# Business_card_rev6.net
KiCad netlist of a schematic drawn in EAGLE
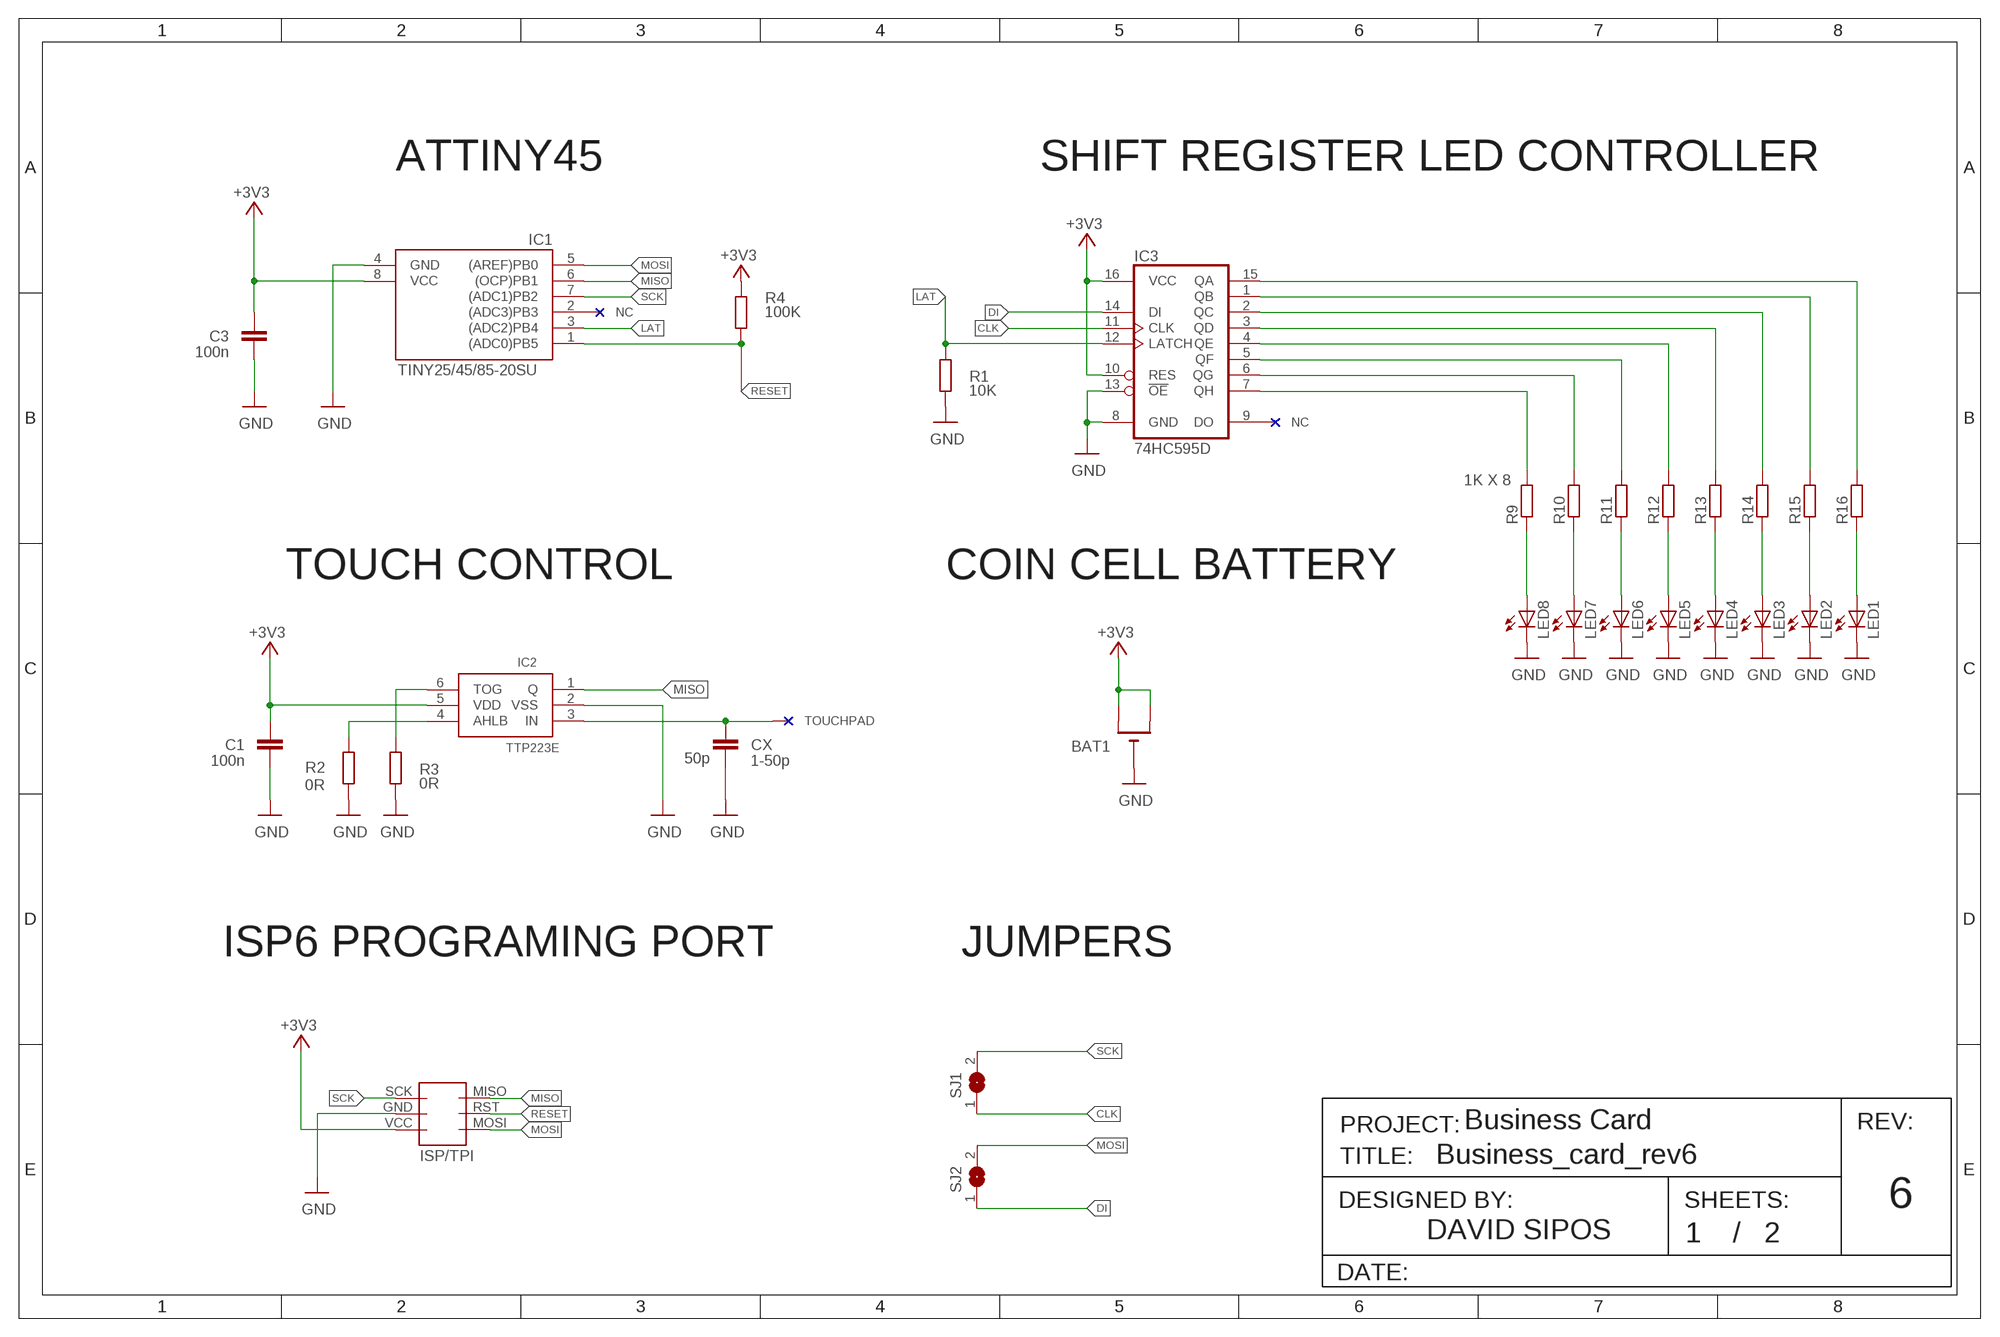
[diagram p0: schematic, sheet 1]
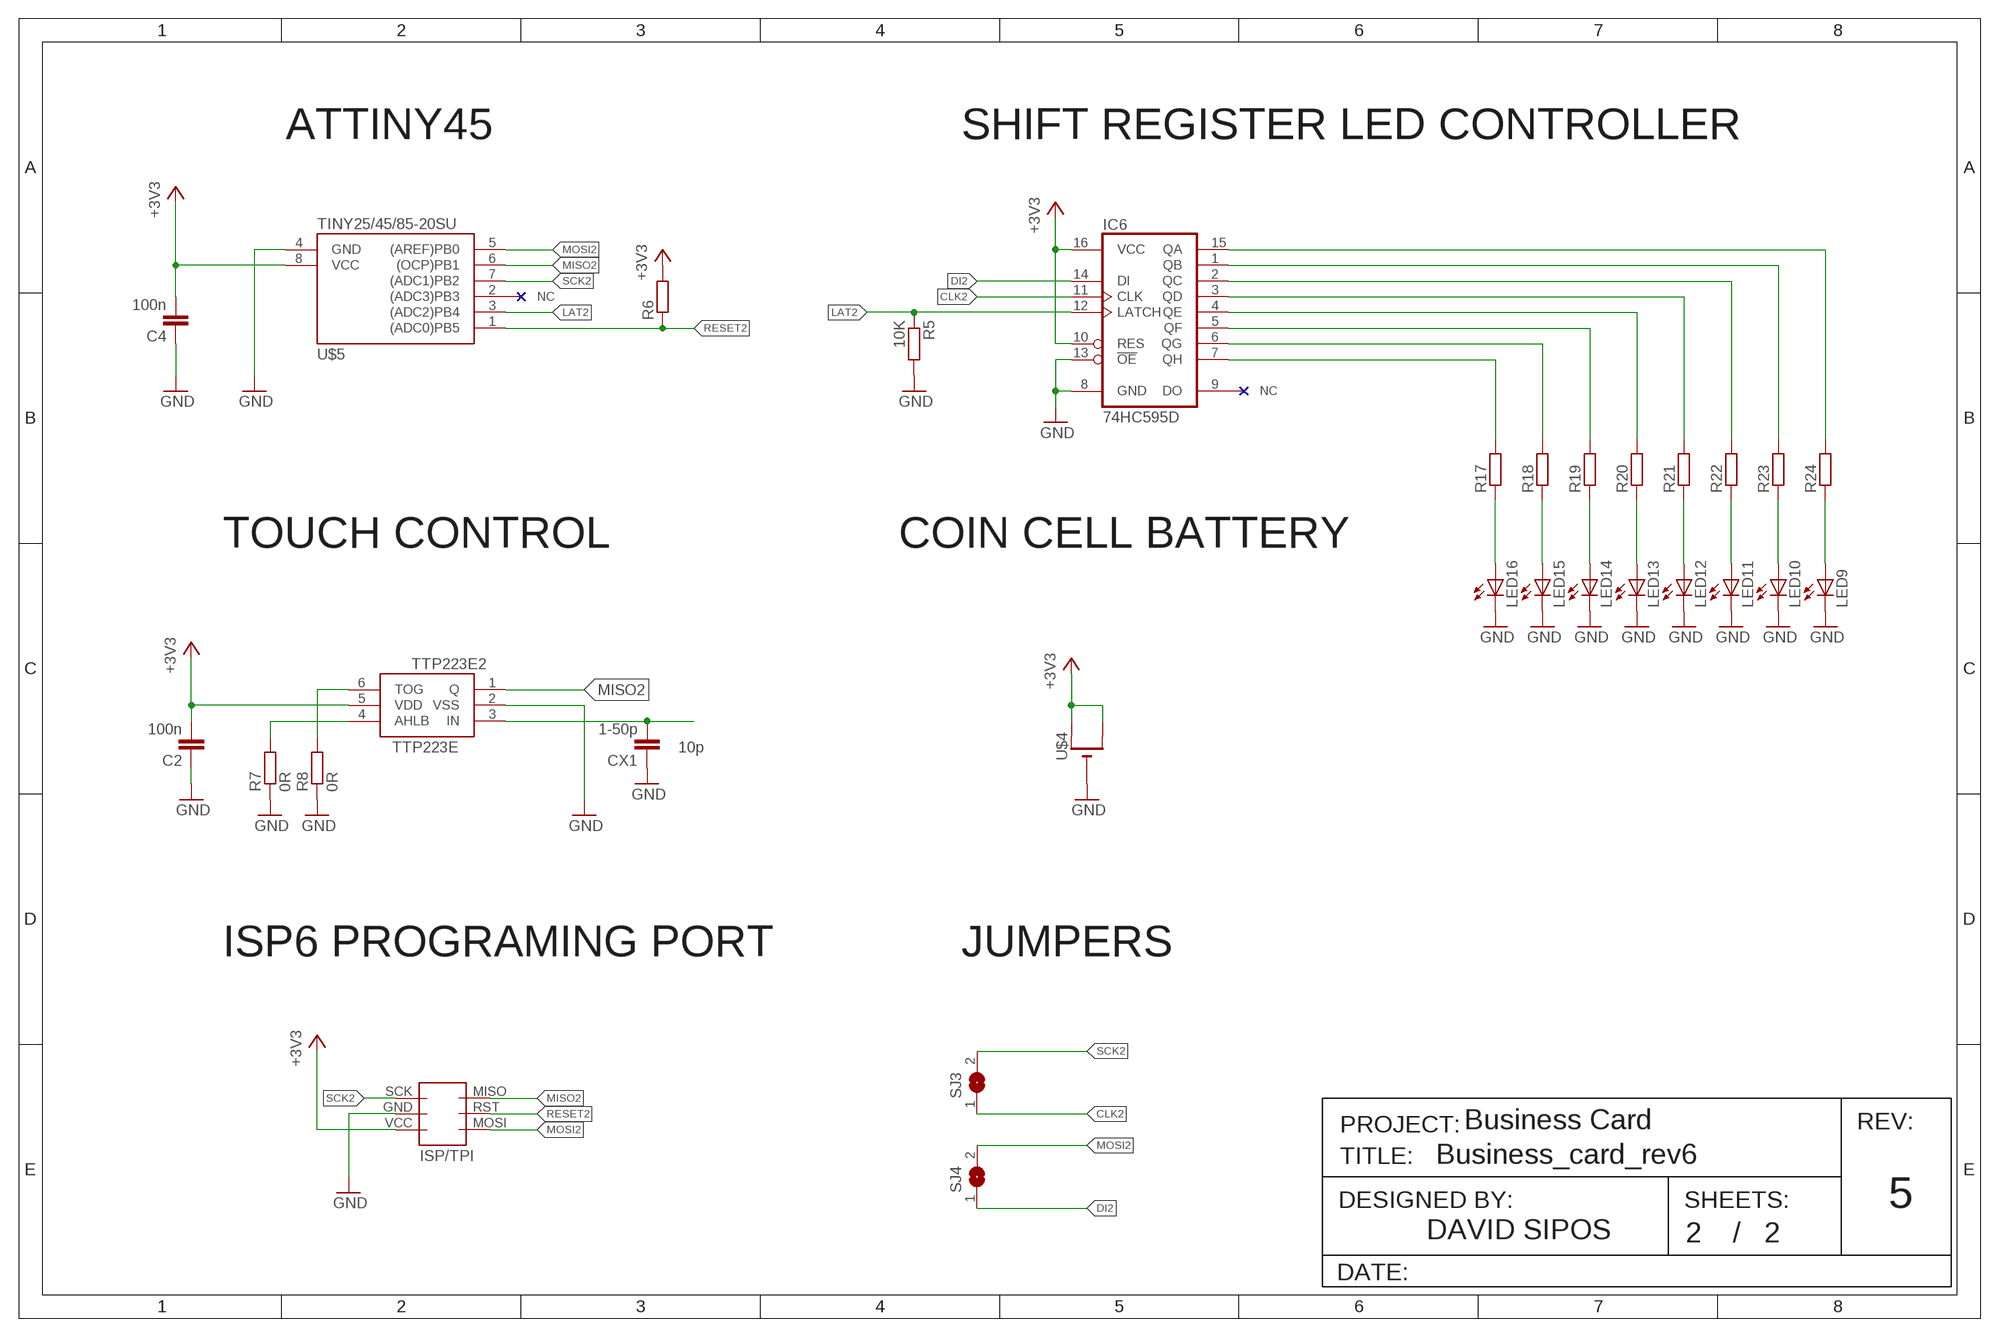
[diagram p1: schematic, sheet 2]

(export (version "E")
  (design (tool "Eeschema 10.0.6"))
  (components
    (comp (ref "BAT1")
      (value "CR2032SMT")
      (footprint "eagle-import:CR2032-SMD")
      (libsource (lib "eagle-import") (part "CR2032SMT"))
    )
    (comp (ref "C1")
      (value "100n")
      (footprint "eagle-import:C1206K")
      (libsource (lib "eagle-import") (part "C-EUC1206K"))
    )
    (comp (ref "C3")
      (value "100n")
      (footprint "eagle-import:C1206K")
      (libsource (lib "eagle-import") (part "C-EUC1206K"))
    )
    (comp (ref "CX")
      (value "1-50p")
      (footprint "eagle-import:C1206K")
      (libsource (lib "eagle-import") (part "C-EUC1206K"))
    )
    (comp (ref "IC1")
      (value "TINY25/45/85-20SU")
      (footprint "eagle-import:SOIC8")
      (libsource (lib "eagle-import") (part "TINY25/45/85-20SU"))
    )
    (comp (ref "IC2")
      (value "TTP223E")
      (footprint "eagle-import:SOT23-6")
      (libsource (lib "eagle-import") (part "TTP223E"))
    )
    (comp (ref "IC3")
      (value "74HC595D")
      (footprint "eagle-import:SO16")
      (libsource (lib "eagle-import") (part "74595DHC"))
    )
    (comp (ref "LED1")
      (value "LEDCHIPLED_0805")
      (footprint "eagle-import:CHIPLED_0805")
      (libsource (lib "eagle-import") (part "LEDCHIPLED_0805"))
    )
    (comp (ref "LED2")
      (value "LEDCHIPLED_0805")
      (footprint "eagle-import:CHIPLED_0805")
      (libsource (lib "eagle-import") (part "LEDCHIPLED_0805"))
    )
    (comp (ref "LED3")
      (value "LEDCHIPLED_0805")
      (footprint "eagle-import:CHIPLED_0805")
      (libsource (lib "eagle-import") (part "LEDCHIPLED_0805"))
    )
    (comp (ref "LED4")
      (value "LEDCHIPLED_0805")
      (footprint "eagle-import:CHIPLED_0805")
      (libsource (lib "eagle-import") (part "LEDCHIPLED_0805"))
    )
    (comp (ref "LED5")
      (value "LEDCHIPLED_0805")
      (footprint "eagle-import:CHIPLED_0805")
      (libsource (lib "eagle-import") (part "LEDCHIPLED_0805"))
    )
    (comp (ref "LED6")
      (value "LEDCHIPLED_0805")
      (footprint "eagle-import:CHIPLED_0805")
      (libsource (lib "eagle-import") (part "LEDCHIPLED_0805"))
    )
    (comp (ref "LED7")
      (value "LEDCHIPLED_0805")
      (footprint "eagle-import:CHIPLED_0805")
      (libsource (lib "eagle-import") (part "LEDCHIPLED_0805"))
    )
    (comp (ref "LED8")
      (value "LEDCHIPLED_0805")
      (footprint "eagle-import:CHIPLED_0805")
      (libsource (lib "eagle-import") (part "LEDCHIPLED_0805"))
    )
    (comp (ref "R1")
      (value "10K")
      (footprint "eagle-import:M0805")
      (libsource (lib "eagle-import") (part "R-EU_M0805"))
    )
    (comp (ref "R2")
      (value "0R")
      (footprint "eagle-import:M0805")
      (libsource (lib "eagle-import") (part "R-EU_M0805"))
    )
    (comp (ref "R3")
      (value "0R")
      (footprint "eagle-import:M0805")
      (libsource (lib "eagle-import") (part "R-EU_M0805"))
    )
    (comp (ref "R4")
      (value "100K")
      (footprint "eagle-import:M0805")
      (libsource (lib "eagle-import") (part "R-EU_M0805"))
    )
    (comp (ref "R9")
      (value "R-EU_M0805")
      (footprint "eagle-import:M0805")
      (libsource (lib "eagle-import") (part "R-EU_M0805"))
    )
    (comp (ref "R10")
      (value "R-EU_M0805")
      (footprint "eagle-import:M0805")
      (libsource (lib "eagle-import") (part "R-EU_M0805"))
    )
    (comp (ref "R11")
      (value "R-EU_M0805")
      (footprint "eagle-import:M0805")
      (libsource (lib "eagle-import") (part "R-EU_M0805"))
    )
    (comp (ref "R12")
      (value "R-EU_M0805")
      (footprint "eagle-import:M0805")
      (libsource (lib "eagle-import") (part "R-EU_M0805"))
    )
    (comp (ref "R13")
      (value "R-EU_M0805")
      (footprint "eagle-import:M0805")
      (libsource (lib "eagle-import") (part "R-EU_M0805"))
    )
    (comp (ref "R14")
      (value "R-EU_M0805")
      (footprint "eagle-import:M0805")
      (libsource (lib "eagle-import") (part "R-EU_M0805"))
    )
    (comp (ref "R15")
      (value "R-EU_M0805")
      (footprint "eagle-import:M0805")
      (libsource (lib "eagle-import") (part "R-EU_M0805"))
    )
    (comp (ref "R16")
      (value "R-EU_M0805")
      (footprint "eagle-import:M0805")
      (libsource (lib "eagle-import") (part "R-EU_M0805"))
    )
    (comp (ref "SJ1") (value "SJ") (footprint "eagle-import:SJ") (libsource (lib "eagle-import") (part "SJ")))
    (comp (ref "SJ2") (value "SJ") (footprint "eagle-import:SJ") (libsource (lib "eagle-import") (part "SJ")))
    (comp (ref "U$11")
      (value "AVR-ISP-6-EDGE")
      (footprint "eagle-import:6PAD_ISP")
      (libsource (lib "eagle-import") (part "AVR-ISP-6-EDGE"))
    )
    (comp (ref "C2")
      (value "100n")
      (footprint "eagle-import:C1206K")
      (libsource (lib "eagle-import") (part "C-EUC1206K"))
    )
    (comp (ref "C4")
      (value "100n")
      (footprint "eagle-import:C1206K")
      (libsource (lib "eagle-import") (part "C-EUC1206K"))
    )
    (comp (ref "CX1")
      (value "1-50p")
      (footprint "eagle-import:C1206K")
      (libsource (lib "eagle-import") (part "C-EUC1206K"))
    )
    (comp (ref "IC6")
      (value "74HC595D")
      (footprint "eagle-import:SO16")
      (libsource (lib "eagle-import") (part "74595DHC"))
    )
    (comp (ref "LED9")
      (value "LEDCHIPLED_0805")
      (footprint "eagle-import:CHIPLED_0805")
      (libsource (lib "eagle-import") (part "LEDCHIPLED_0805"))
    )
    (comp (ref "LED10")
      (value "LEDCHIPLED_0805")
      (footprint "eagle-import:CHIPLED_0805")
      (libsource (lib "eagle-import") (part "LEDCHIPLED_0805"))
    )
    (comp (ref "LED11")
      (value "LEDCHIPLED_0805")
      (footprint "eagle-import:CHIPLED_0805")
      (libsource (lib "eagle-import") (part "LEDCHIPLED_0805"))
    )
    (comp (ref "LED12")
      (value "LEDCHIPLED_0805")
      (footprint "eagle-import:CHIPLED_0805")
      (libsource (lib "eagle-import") (part "LEDCHIPLED_0805"))
    )
    (comp (ref "LED13")
      (value "LEDCHIPLED_0805")
      (footprint "eagle-import:CHIPLED_0805")
      (libsource (lib "eagle-import") (part "LEDCHIPLED_0805"))
    )
    (comp (ref "LED14")
      (value "LEDCHIPLED_0805")
      (footprint "eagle-import:CHIPLED_0805")
      (libsource (lib "eagle-import") (part "LEDCHIPLED_0805"))
    )
    (comp (ref "LED15")
      (value "LEDCHIPLED_0805")
      (footprint "eagle-import:CHIPLED_0805")
      (libsource (lib "eagle-import") (part "LEDCHIPLED_0805"))
    )
    (comp (ref "LED16")
      (value "LEDCHIPLED_0805")
      (footprint "eagle-import:CHIPLED_0805")
      (libsource (lib "eagle-import") (part "LEDCHIPLED_0805"))
    )
    (comp (ref "R5")
      (value "10K")
      (footprint "eagle-import:M0805")
      (libsource (lib "eagle-import") (part "R-EU_M0805"))
    )
    (comp (ref "R6")
      (value "R-EU_M0805")
      (footprint "eagle-import:M0805")
      (libsource (lib "eagle-import") (part "R-EU_M0805"))
    )
    (comp (ref "R7")
      (value "0R")
      (footprint "eagle-import:M0805")
      (libsource (lib "eagle-import") (part "R-EU_M0805"))
    )
    (comp (ref "R8")
      (value "0R")
      (footprint "eagle-import:M0805")
      (libsource (lib "eagle-import") (part "R-EU_M0805"))
    )
    (comp (ref "R17")
      (value "R-EU_M0805")
      (footprint "eagle-import:M0805")
      (libsource (lib "eagle-import") (part "R-EU_M0805"))
    )
    (comp (ref "R18")
      (value "R-EU_M0805")
      (footprint "eagle-import:M0805")
      (libsource (lib "eagle-import") (part "R-EU_M0805"))
    )
    (comp (ref "R19")
      (value "R-EU_M0805")
      (footprint "eagle-import:M0805")
      (libsource (lib "eagle-import") (part "R-EU_M0805"))
    )
    (comp (ref "R20")
      (value "R-EU_M0805")
      (footprint "eagle-import:M0805")
      (libsource (lib "eagle-import") (part "R-EU_M0805"))
    )
    (comp (ref "R21")
      (value "R-EU_M0805")
      (footprint "eagle-import:M0805")
      (libsource (lib "eagle-import") (part "R-EU_M0805"))
    )
    (comp (ref "R22")
      (value "R-EU_M0805")
      (footprint "eagle-import:M0805")
      (libsource (lib "eagle-import") (part "R-EU_M0805"))
    )
    (comp (ref "R23")
      (value "R-EU_M0805")
      (footprint "eagle-import:M0805")
      (libsource (lib "eagle-import") (part "R-EU_M0805"))
    )
    (comp (ref "R24")
      (value "R-EU_M0805")
      (footprint "eagle-import:M0805")
      (libsource (lib "eagle-import") (part "R-EU_M0805"))
    )
    (comp (ref "SJ3") (value "SJ") (footprint "eagle-import:SJ") (libsource (lib "eagle-import") (part "SJ")))
    (comp (ref "SJ4") (value "SJ") (footprint "eagle-import:SJ") (libsource (lib "eagle-import") (part "SJ")))
    (comp (ref "TTP223E2")
      (value "TTP223E")
      (footprint "eagle-import:SOT23-6")
      (libsource (lib "eagle-import") (part "TTP223E"))
    )
    (comp (ref "U$4")
      (value "CR2032SMT")
      (footprint "eagle-import:CR2032-SMD")
      (libsource (lib "eagle-import") (part "CR2032SMT"))
    )
    (comp (ref "U$5")
      (value "TINY25/45/85-20SU")
      (footprint "eagle-import:SOIC8")
      (libsource (lib "eagle-import") (part "TINY25/45/85-20SU"))
    )
    (comp (ref "U$12")
      (value "AVR-ISP-6-EDGE")
      (footprint "eagle-import:6PAD_ISP")
      (libsource (lib "eagle-import") (part "AVR-ISP-6-EDGE"))
    )
  )
  (nets
    (net (code "1") (name "+3V3") (class "Default")
      (node (ref "BAT1") (pin "+$1") (pinfunction "+_+$1") (pintype "passive"))
      (node (ref "BAT1") (pin "+$2") (pinfunction "+1_+$2") (pintype "passive"))
      (node (ref "C1") (pin "2") (pinfunction "2_2") (pintype "passive"))
      (node (ref "C2") (pin "2") (pinfunction "2_2") (pintype "passive"))
      (node (ref "C3") (pin "2") (pinfunction "2_2") (pintype "passive"))
      (node (ref "C4") (pin "2") (pinfunction "2_2") (pintype "passive"))
      (node (ref "IC1") (pin "8") (pinfunction "VCC_8") (pintype "power_in"))
      (node (ref "IC2") (pin "5") (pinfunction "VDD_5") (pintype "bidirectional"))
      (node (ref "IC3") (pin "10") (pinfunction "RES_10") (pintype "input"))
      (node (ref "IC3") (pin "16") (pinfunction "VCC_16") (pintype "power_in"))
      (node (ref "IC6") (pin "10") (pinfunction "RES_10") (pintype "input"))
      (node (ref "IC6") (pin "16") (pinfunction "VCC_16") (pintype "power_in"))
      (node (ref "R4") (pin "2") (pinfunction "2_2") (pintype "passive"))
      (node (ref "R6") (pin "2") (pinfunction "2_2") (pintype "passive"))
      (node (ref "TTP223E2") (pin "5") (pinfunction "VDD_5") (pintype "bidirectional"))
      (node (ref "U$11") (pin "VCC") (pinfunction "P$6_VCC") (pintype "bidirectional"))
      (node (ref "U$12") (pin "VCC") (pinfunction "P$6_VCC") (pintype "bidirectional"))
      (node (ref "U$4") (pin "+$1") (pinfunction "+_+$1") (pintype "passive"))
      (node (ref "U$4") (pin "+$2") (pinfunction "+1_+$2") (pintype "passive"))
      (node (ref "U$5") (pin "8") (pinfunction "VCC_8") (pintype "power_in"))
    )
    (net (code "2") (name "CLK") (class "Default")
      (node (ref "IC3") (pin "11") (pinfunction "CLK_11") (pintype "input"))
      (node (ref "SJ1") (pin "1") (pinfunction "1_1") (pintype "passive"))
    )
    (net (code "3") (name "CLK2") (class "Default")
      (node (ref "IC6") (pin "11") (pinfunction "CLK_11") (pintype "input"))
      (node (ref "SJ3") (pin "1") (pinfunction "1_1") (pintype "passive"))
    )
    (net (code "4") (name "DI") (class "Default")
      (node (ref "IC3") (pin "14") (pinfunction "DI_14") (pintype "input"))
      (node (ref "SJ2") (pin "1") (pinfunction "1_1") (pintype "passive"))
    )
    (net (code "5") (name "DI2") (class "Default")
      (node (ref "IC6") (pin "14") (pinfunction "DI_14") (pintype "input"))
      (node (ref "SJ4") (pin "1") (pinfunction "1_1") (pintype "passive"))
    )
    (net (code "6") (name "GND") (class "Default")
      (node (ref "BAT1") (pin "-") (pinfunction "-_-") (pintype "passive"))
      (node (ref "C1") (pin "1") (pinfunction "1_1") (pintype "passive"))
      (node (ref "C2") (pin "1") (pinfunction "1_1") (pintype "passive"))
      (node (ref "C3") (pin "1") (pinfunction "1_1") (pintype "passive"))
      (node (ref "C4") (pin "1") (pinfunction "1_1") (pintype "passive"))
      (node (ref "CX") (pin "1") (pinfunction "1_1") (pintype "passive"))
      (node (ref "CX1") (pin "1") (pinfunction "1_1") (pintype "passive"))
      (node (ref "IC1") (pin "4") (pinfunction "GND_4") (pintype "power_in"))
      (node (ref "IC2") (pin "2") (pinfunction "VSS_2") (pintype "bidirectional"))
      (node (ref "IC3") (pin "13") (pinfunction "~{OE}_13") (pintype "input"))
      (node (ref "IC3") (pin "8") (pinfunction "GND_8") (pintype "power_in"))
      (node (ref "IC6") (pin "13") (pinfunction "~{OE}_13") (pintype "input"))
      (node (ref "IC6") (pin "8") (pinfunction "GND_8") (pintype "power_in"))
      (node (ref "LED1") (pin "C") (pinfunction "C_C") (pintype "passive"))
      (node (ref "LED10") (pin "C") (pinfunction "C_C") (pintype "passive"))
      (node (ref "LED11") (pin "C") (pinfunction "C_C") (pintype "passive"))
      (node (ref "LED12") (pin "C") (pinfunction "C_C") (pintype "passive"))
      (node (ref "LED13") (pin "C") (pinfunction "C_C") (pintype "passive"))
      (node (ref "LED14") (pin "C") (pinfunction "C_C") (pintype "passive"))
      (node (ref "LED15") (pin "C") (pinfunction "C_C") (pintype "passive"))
      (node (ref "LED16") (pin "C") (pinfunction "C_C") (pintype "passive"))
      (node (ref "LED2") (pin "C") (pinfunction "C_C") (pintype "passive"))
      (node (ref "LED3") (pin "C") (pinfunction "C_C") (pintype "passive"))
      (node (ref "LED4") (pin "C") (pinfunction "C_C") (pintype "passive"))
      (node (ref "LED5") (pin "C") (pinfunction "C_C") (pintype "passive"))
      (node (ref "LED6") (pin "C") (pinfunction "C_C") (pintype "passive"))
      (node (ref "LED7") (pin "C") (pinfunction "C_C") (pintype "passive"))
      (node (ref "LED8") (pin "C") (pinfunction "C_C") (pintype "passive"))
      (node (ref "LED9") (pin "C") (pinfunction "C_C") (pintype "passive"))
      (node (ref "R1") (pin "2") (pinfunction "2_2") (pintype "passive"))
      (node (ref "R2") (pin "1") (pinfunction "1_1") (pintype "passive"))
      (node (ref "R3") (pin "1") (pinfunction "1_1") (pintype "passive"))
      (node (ref "R5") (pin "2") (pinfunction "2_2") (pintype "passive"))
      (node (ref "R7") (pin "1") (pinfunction "1_1") (pintype "passive"))
      (node (ref "R8") (pin "1") (pinfunction "1_1") (pintype "passive"))
      (node (ref "TTP223E2") (pin "2") (pinfunction "VSS_2") (pintype "bidirectional"))
      (node (ref "U$11") (pin "GND") (pinfunction "P$4_GND") (pintype "bidirectional"))
      (node (ref "U$12") (pin "GND") (pinfunction "P$4_GND") (pintype "bidirectional"))
      (node (ref "U$4") (pin "-") (pinfunction "-_-") (pintype "passive"))
      (node (ref "U$5") (pin "4") (pinfunction "GND_4") (pintype "power_in"))
    )
    (net (code "7") (name "LAT") (class "Default")
      (node (ref "IC1") (pin "3") (pinfunction "(ADC2)PB4_3") (pintype "bidirectional"))
      (node (ref "IC3") (pin "12") (pinfunction "LATCH_12") (pintype "input"))
      (node (ref "R1") (pin "1") (pinfunction "1_1") (pintype "passive"))
    )
    (net (code "8") (name "LAT2") (class "Default")
      (node (ref "IC6") (pin "12") (pinfunction "LATCH_12") (pintype "input"))
      (node (ref "R5") (pin "1") (pinfunction "1_1") (pintype "passive"))
      (node (ref "U$5") (pin "3") (pinfunction "(ADC2)PB4_3") (pintype "bidirectional"))
    )
    (net (code "9") (name "MISO") (class "Default")
      (node (ref "IC1") (pin "6") (pinfunction "(OCP)PB1_6") (pintype "bidirectional"))
      (node (ref "IC2") (pin "1") (pinfunction "Q_1") (pintype "bidirectional"))
      (node (ref "U$11") (pin "MISO") (pinfunction "P$1_MISO") (pintype "bidirectional"))
    )
    (net (code "10") (name "MISO2") (class "Default")
      (node (ref "TTP223E2") (pin "1") (pinfunction "Q_1") (pintype "bidirectional"))
      (node (ref "U$12") (pin "MISO") (pinfunction "P$1_MISO") (pintype "bidirectional"))
      (node (ref "U$5") (pin "6") (pinfunction "(OCP)PB1_6") (pintype "bidirectional"))
    )
    (net (code "11") (name "MOSI") (class "Default")
      (node (ref "IC1") (pin "5") (pinfunction "(AREF)PB0_5") (pintype "bidirectional"))
      (node (ref "SJ2") (pin "2") (pinfunction "2_2") (pintype "passive"))
      (node (ref "U$11") (pin "MOSI") (pinfunction "P$5_MOSI") (pintype "bidirectional"))
    )
    (net (code "12") (name "MOSI2") (class "Default")
      (node (ref "SJ4") (pin "2") (pinfunction "2_2") (pintype "passive"))
      (node (ref "U$12") (pin "MOSI") (pinfunction "P$5_MOSI") (pintype "bidirectional"))
      (node (ref "U$5") (pin "5") (pinfunction "(AREF)PB0_5") (pintype "bidirectional"))
    )
    (net (code "13") (name "Net-(IC2-AHLB)") (class "Default")
      (node (ref "IC2") (pin "4") (pinfunction "AHLB_4") (pintype "bidirectional"))
      (node (ref "R2") (pin "2") (pinfunction "2_2") (pintype "passive"))
    )
    (net (code "14") (name "Net-(IC2-IN)") (class "Default")
      (node (ref "CX") (pin "2") (pinfunction "2_2") (pintype "passive"))
      (node (ref "IC2") (pin "3") (pinfunction "IN_3") (pintype "bidirectional"))
    )
    (net (code "15") (name "Net-(IC2-TOG)") (class "Default")
      (node (ref "IC2") (pin "6") (pinfunction "TOG_6") (pintype "bidirectional"))
      (node (ref "R3") (pin "2") (pinfunction "2_2") (pintype "passive"))
    )
    (net (code "16") (name "Net-(IC3-QA)") (class "Default")
      (node (ref "IC3") (pin "15") (pinfunction "QA_15") (pintype "tri_state"))
      (node (ref "R16") (pin "2") (pinfunction "2_2") (pintype "passive"))
    )
    (net (code "17") (name "Net-(IC3-QB)") (class "Default")
      (node (ref "IC3") (pin "1") (pinfunction "QB_1") (pintype "tri_state"))
      (node (ref "R15") (pin "2") (pinfunction "2_2") (pintype "passive"))
    )
    (net (code "18") (name "Net-(IC3-QC)") (class "Default")
      (node (ref "IC3") (pin "2") (pinfunction "QC_2") (pintype "tri_state"))
      (node (ref "R14") (pin "2") (pinfunction "2_2") (pintype "passive"))
    )
    (net (code "19") (name "Net-(IC3-QD)") (class "Default")
      (node (ref "IC3") (pin "3") (pinfunction "QD_3") (pintype "tri_state"))
      (node (ref "R13") (pin "2") (pinfunction "2_2") (pintype "passive"))
    )
    (net (code "20") (name "Net-(IC3-QE)") (class "Default")
      (node (ref "IC3") (pin "4") (pinfunction "QE_4") (pintype "tri_state"))
      (node (ref "R12") (pin "2") (pinfunction "2_2") (pintype "passive"))
    )
    (net (code "21") (name "Net-(IC3-QF)") (class "Default")
      (node (ref "IC3") (pin "5") (pinfunction "QF_5") (pintype "tri_state"))
      (node (ref "R11") (pin "2") (pinfunction "2_2") (pintype "passive"))
    )
    (net (code "22") (name "Net-(IC3-QG)") (class "Default")
      (node (ref "IC3") (pin "6") (pinfunction "QG_6") (pintype "tri_state"))
      (node (ref "R10") (pin "2") (pinfunction "2_2") (pintype "passive"))
    )
    (net (code "23") (name "Net-(IC3-QH)") (class "Default")
      (node (ref "IC3") (pin "7") (pinfunction "QH_7") (pintype "tri_state"))
      (node (ref "R9") (pin "2") (pinfunction "2_2") (pintype "passive"))
    )
    (net (code "24") (name "Net-(IC6-QA)") (class "Default")
      (node (ref "IC6") (pin "15") (pinfunction "QA_15") (pintype "tri_state"))
      (node (ref "R24") (pin "2") (pinfunction "2_2") (pintype "passive"))
    )
    (net (code "25") (name "Net-(IC6-QB)") (class "Default")
      (node (ref "IC6") (pin "1") (pinfunction "QB_1") (pintype "tri_state"))
      (node (ref "R23") (pin "2") (pinfunction "2_2") (pintype "passive"))
    )
    (net (code "26") (name "Net-(IC6-QC)") (class "Default")
      (node (ref "IC6") (pin "2") (pinfunction "QC_2") (pintype "tri_state"))
      (node (ref "R22") (pin "2") (pinfunction "2_2") (pintype "passive"))
    )
    (net (code "27") (name "Net-(IC6-QD)") (class "Default")
      (node (ref "IC6") (pin "3") (pinfunction "QD_3") (pintype "tri_state"))
      (node (ref "R21") (pin "2") (pinfunction "2_2") (pintype "passive"))
    )
    (net (code "28") (name "Net-(IC6-QE)") (class "Default")
      (node (ref "IC6") (pin "4") (pinfunction "QE_4") (pintype "tri_state"))
      (node (ref "R20") (pin "2") (pinfunction "2_2") (pintype "passive"))
    )
    (net (code "29") (name "Net-(IC6-QF)") (class "Default")
      (node (ref "IC6") (pin "5") (pinfunction "QF_5") (pintype "tri_state"))
      (node (ref "R19") (pin "2") (pinfunction "2_2") (pintype "passive"))
    )
    (net (code "30") (name "Net-(IC6-QG)") (class "Default")
      (node (ref "IC6") (pin "6") (pinfunction "QG_6") (pintype "tri_state"))
      (node (ref "R18") (pin "2") (pinfunction "2_2") (pintype "passive"))
    )
    (net (code "31") (name "Net-(IC6-QH)") (class "Default")
      (node (ref "IC6") (pin "7") (pinfunction "QH_7") (pintype "tri_state"))
      (node (ref "R17") (pin "2") (pinfunction "2_2") (pintype "passive"))
    )
    (net (code "32") (name "Net-(LED1-PadA)") (class "Default")
      (node (ref "LED1") (pin "A") (pinfunction "A_A") (pintype "passive"))
      (node (ref "R16") (pin "1") (pinfunction "1_1") (pintype "passive"))
    )
    (net (code "33") (name "Net-(LED2-PadA)") (class "Default")
      (node (ref "LED2") (pin "A") (pinfunction "A_A") (pintype "passive"))
      (node (ref "R15") (pin "1") (pinfunction "1_1") (pintype "passive"))
    )
    (net (code "34") (name "Net-(LED3-PadA)") (class "Default")
      (node (ref "LED3") (pin "A") (pinfunction "A_A") (pintype "passive"))
      (node (ref "R14") (pin "1") (pinfunction "1_1") (pintype "passive"))
    )
    (net (code "35") (name "Net-(LED4-PadA)") (class "Default")
      (node (ref "LED4") (pin "A") (pinfunction "A_A") (pintype "passive"))
      (node (ref "R13") (pin "1") (pinfunction "1_1") (pintype "passive"))
    )
    (net (code "36") (name "Net-(LED5-PadA)") (class "Default")
      (node (ref "LED5") (pin "A") (pinfunction "A_A") (pintype "passive"))
      (node (ref "R12") (pin "1") (pinfunction "1_1") (pintype "passive"))
    )
    (net (code "37") (name "Net-(LED6-PadA)") (class "Default")
      (node (ref "LED6") (pin "A") (pinfunction "A_A") (pintype "passive"))
      (node (ref "R11") (pin "1") (pinfunction "1_1") (pintype "passive"))
    )
    (net (code "38") (name "Net-(LED7-PadA)") (class "Default")
      (node (ref "LED7") (pin "A") (pinfunction "A_A") (pintype "passive"))
      (node (ref "R10") (pin "1") (pinfunction "1_1") (pintype "passive"))
    )
    (net (code "39") (name "Net-(LED8-PadA)") (class "Default")
      (node (ref "LED8") (pin "A") (pinfunction "A_A") (pintype "passive"))
      (node (ref "R9") (pin "1") (pinfunction "1_1") (pintype "passive"))
    )
    (net (code "40") (name "Net-(LED9-PadA)") (class "Default")
      (node (ref "LED9") (pin "A") (pinfunction "A_A") (pintype "passive"))
      (node (ref "R24") (pin "1") (pinfunction "1_1") (pintype "passive"))
    )
    (net (code "41") (name "Net-(LED10-PadA)") (class "Default")
      (node (ref "LED10") (pin "A") (pinfunction "A_A") (pintype "passive"))
      (node (ref "R23") (pin "1") (pinfunction "1_1") (pintype "passive"))
    )
    (net (code "42") (name "Net-(LED11-PadA)") (class "Default")
      (node (ref "LED11") (pin "A") (pinfunction "A_A") (pintype "passive"))
      (node (ref "R22") (pin "1") (pinfunction "1_1") (pintype "passive"))
    )
    (net (code "43") (name "Net-(LED12-PadA)") (class "Default")
      (node (ref "LED12") (pin "A") (pinfunction "A_A") (pintype "passive"))
      (node (ref "R21") (pin "1") (pinfunction "1_1") (pintype "passive"))
    )
    (net (code "44") (name "Net-(LED13-PadA)") (class "Default")
      (node (ref "LED13") (pin "A") (pinfunction "A_A") (pintype "passive"))
      (node (ref "R20") (pin "1") (pinfunction "1_1") (pintype "passive"))
    )
    (net (code "45") (name "Net-(LED14-PadA)") (class "Default")
      (node (ref "LED14") (pin "A") (pinfunction "A_A") (pintype "passive"))
      (node (ref "R19") (pin "1") (pinfunction "1_1") (pintype "passive"))
    )
    (net (code "46") (name "Net-(LED15-PadA)") (class "Default")
      (node (ref "LED15") (pin "A") (pinfunction "A_A") (pintype "passive"))
      (node (ref "R18") (pin "1") (pinfunction "1_1") (pintype "passive"))
    )
    (net (code "47") (name "Net-(LED16-PadA)") (class "Default")
      (node (ref "LED16") (pin "A") (pinfunction "A_A") (pintype "passive"))
      (node (ref "R17") (pin "1") (pinfunction "1_1") (pintype "passive"))
    )
    (net (code "48") (name "Net-(TTP223E2-AHLB)") (class "Default")
      (node (ref "R7") (pin "2") (pinfunction "2_2") (pintype "passive"))
      (node (ref "TTP223E2") (pin "4") (pinfunction "AHLB_4") (pintype "bidirectional"))
    )
    (net (code "49") (name "Net-(TTP223E2-IN)") (class "Default")
      (node (ref "CX1") (pin "2") (pinfunction "2_2") (pintype "passive"))
      (node (ref "TTP223E2") (pin "3") (pinfunction "IN_3") (pintype "bidirectional"))
    )
    (net (code "50") (name "Net-(TTP223E2-TOG)") (class "Default")
      (node (ref "R8") (pin "2") (pinfunction "2_2") (pintype "passive"))
      (node (ref "TTP223E2") (pin "6") (pinfunction "TOG_6") (pintype "bidirectional"))
    )
    (net (code "51") (name "RESET") (class "Default")
      (node (ref "IC1") (pin "1") (pinfunction "(ADC0)PB5_1") (pintype "bidirectional"))
      (node (ref "R4") (pin "1") (pinfunction "1_1") (pintype "passive"))
      (node (ref "U$11") (pin "RST") (pinfunction "P$3_RST") (pintype "bidirectional"))
    )
    (net (code "52") (name "RESET2") (class "Default")
      (node (ref "R6") (pin "1") (pinfunction "1_1") (pintype "passive"))
      (node (ref "U$12") (pin "RST") (pinfunction "P$3_RST") (pintype "bidirectional"))
      (node (ref "U$5") (pin "1") (pinfunction "(ADC0)PB5_1") (pintype "bidirectional"))
    )
    (net (code "53") (name "SCK") (class "Default")
      (node (ref "IC1") (pin "7") (pinfunction "(ADC1)PB2_7") (pintype "bidirectional"))
      (node (ref "SJ1") (pin "2") (pinfunction "2_2") (pintype "passive"))
      (node (ref "U$11") (pin "SCK") (pinfunction "P$2_SCK") (pintype "bidirectional"))
    )
    (net (code "54") (name "SCK2") (class "Default")
      (node (ref "SJ3") (pin "2") (pinfunction "2_2") (pintype "passive"))
      (node (ref "U$12") (pin "SCK") (pinfunction "P$2_SCK") (pintype "bidirectional"))
      (node (ref "U$5") (pin "7") (pinfunction "(ADC1)PB2_7") (pintype "bidirectional"))
    )
    (net (code "55") (name "unconnected-(IC1-(ADC3)PB3-Pad2)") (class "Default")
      (node (ref "IC1") (pin "2") (pinfunction "(ADC3)PB3_2") (pintype "bidirectional"))
    )
    (net (code "56") (name "unconnected-(IC3-DO-Pad9)") (class "Default")
      (node (ref "IC3") (pin "9") (pinfunction "DO_9") (pintype "tri_state"))
    )
    (net (code "57") (name "unconnected-(IC6-DO-Pad9)") (class "Default")
      (node (ref "IC6") (pin "9") (pinfunction "DO_9") (pintype "tri_state"))
    )
    (net (code "58") (name "unconnected-(U$5-(ADC3)PB3-Pad2)") (class "Default")
      (node (ref "U$5") (pin "2") (pinfunction "(ADC3)PB3_2") (pintype "bidirectional"))
    )
  )
)
